# Top.net
KiCad netlist of a schematic drawn in Altium Designer
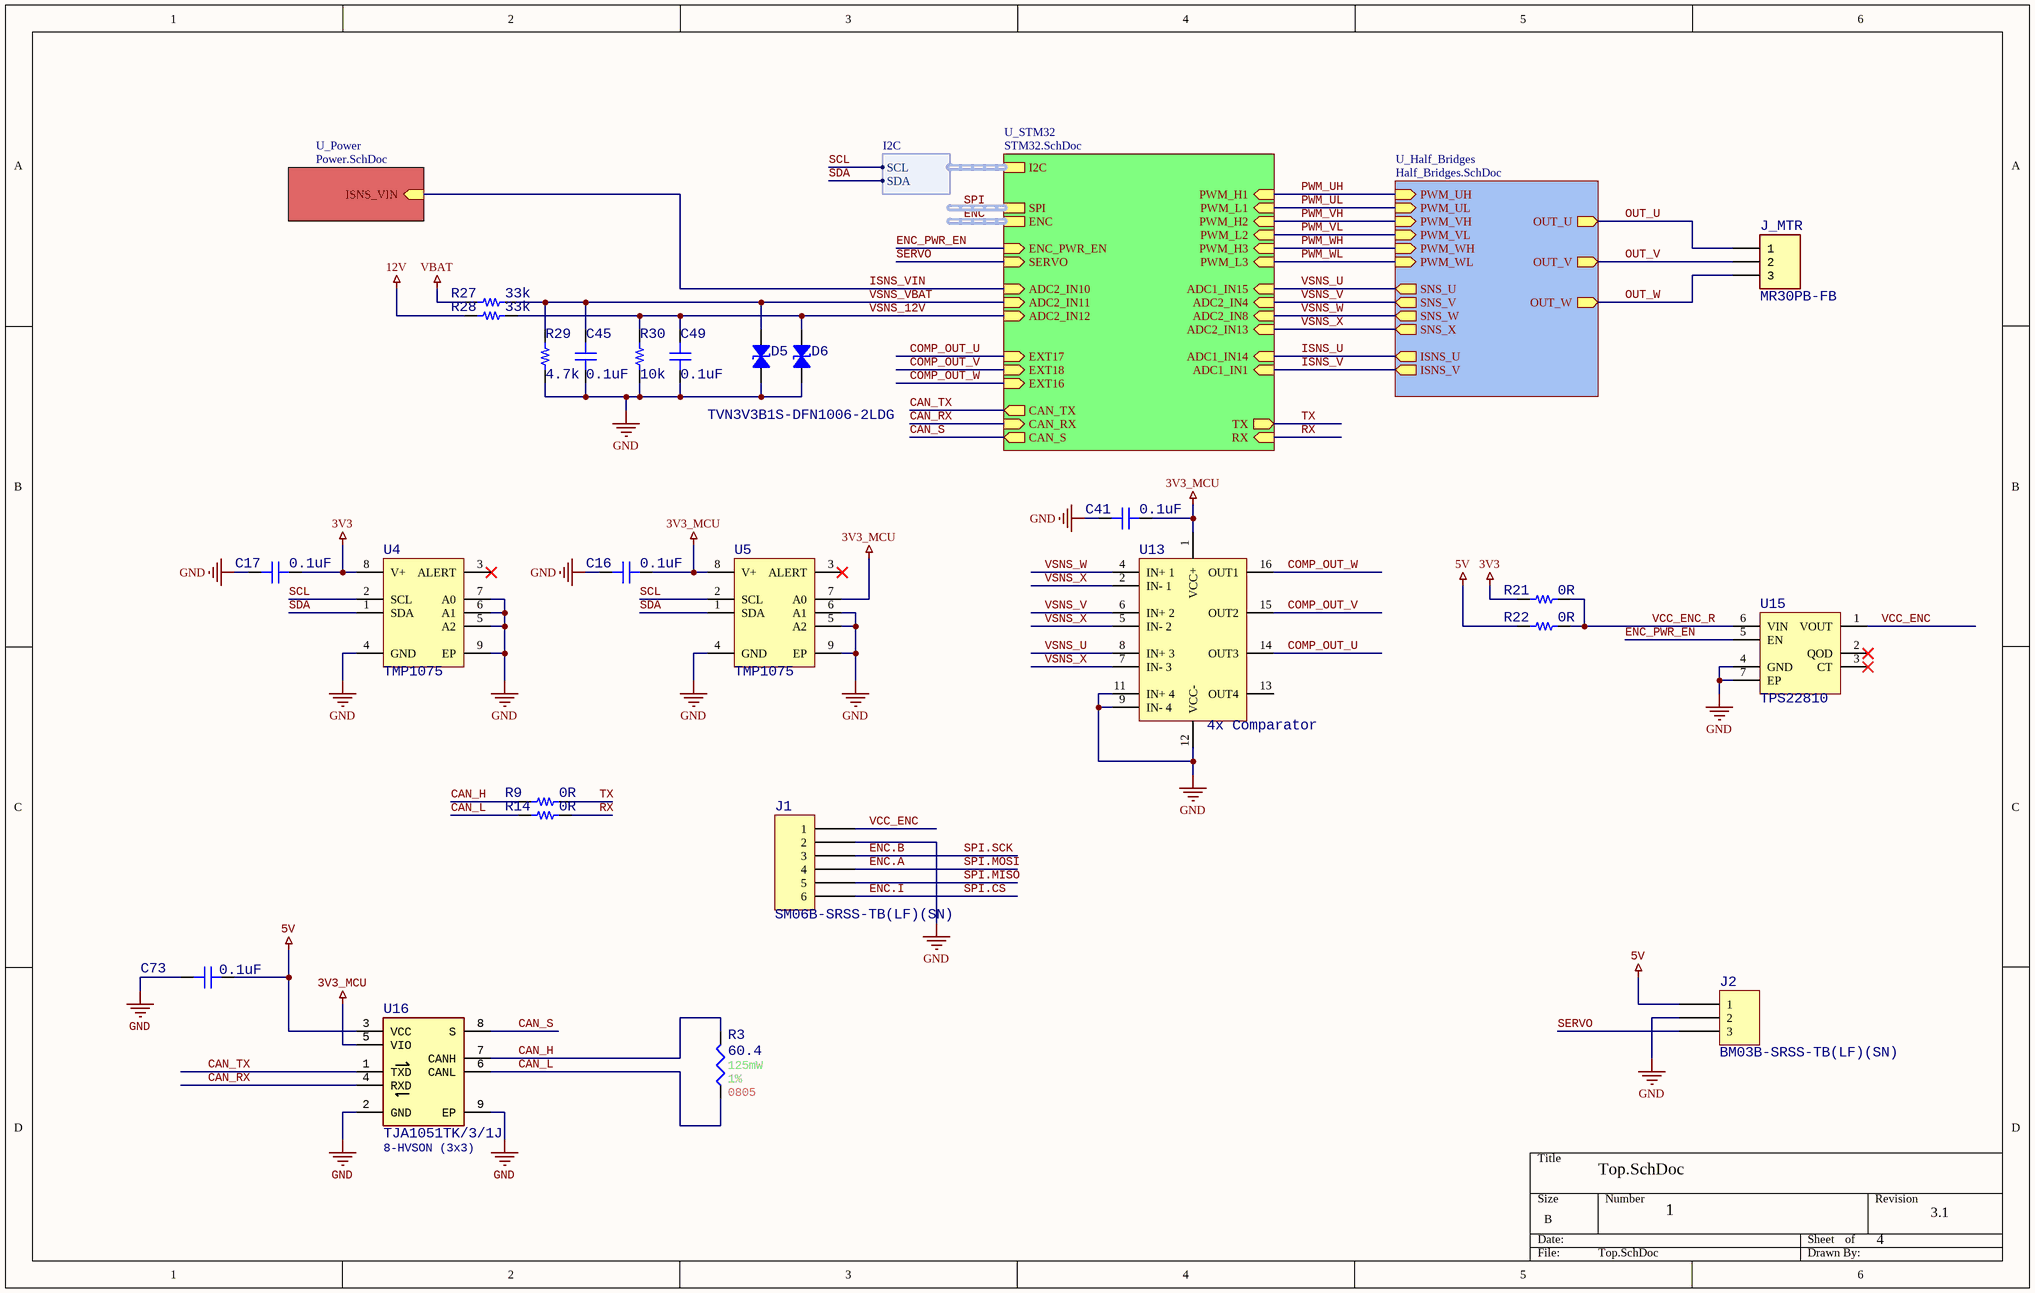
[diagram p0: Top.SchDoc]

(export (version "E")
  (design (tool "Eeschema 10.0.6"))
  (components
    (comp (ref "C16")
      (value "0.1uF")
      (footprint "CAP_0402")
      (description "CAP CER 402")
      (libsource (lib "IC") (part "CAP_0402"))
    )
    (comp (ref "C17")
      (value "0.1uF")
      (footprint "CAP_0402")
      (description "CAP CER 402")
      (libsource (lib "IC") (part "CAP_0402"))
    )
    (comp (ref "C41")
      (value "0.1uF")
      (footprint "CAP_0402")
      (description "CAP CER 402")
      (libsource (lib "IC") (part "CAP_0402"))
    )
    (comp (ref "C45")
      (value "0.1uF")
      (footprint "CAP_0402")
      (description "CAP CER 402")
      (libsource (lib "IC") (part "CAP_0402"))
    )
    (comp (ref "C49")
      (value "0.1uF")
      (footprint "CAP_0402")
      (description "CAP CER 402")
      (libsource (lib "IC") (part "CAP_0402"))
    )
    (comp (ref "C73")
      (value "0.1uF")
      (footprint "CAP_0402")
      (description "CAP CER 402")
      (libsource (lib "IC") (part "CAP_0402"))
    )
    (comp (ref "D5")
      (value "TVN3V3B1S-DFN1006-2LDG")
      (footprint "0402")
      (description "TVS DIODE 3.3V 14.2PF DFN1006")
      (fields (field (name "MANUFACTURER") "INPAQ Technology Co., Ltd"))
      (libsource (lib "Celestial Altium Library - altium_library") (part "Diode TVS"))
    )
    (comp (ref "D6")
      (value "TVN3V3B1S-DFN1006-2LDG")
      (footprint "0402")
      (description "TVS DIODE 3.3V 14.2PF DFN1006")
      (fields (field (name "MANUFACTURER") "INPAQ Technology Co., Ltd"))
      (libsource (lib "Celestial Altium Library - altium_library") (part "Diode TVS"))
    )
    (comp (ref "J1")
      (value "SM06B-SRSS-TB(LF)(SN)")
      (footprint "JST SM06B-SRSS-TB")
      (description "CONN HEADER SMD R/A 6POS 1MM")
      (fields (field (name "MANUFACTURER") "JST Sales America Inc."))
      (libsource (lib "Celestial Altium Library - altium_library") (part "6 Pin"))
    )
    (comp (ref "J2")
      (value "BM03B-SRSS-TB(LF)(SN)")
      (footprint "JST BM03B-SRSS-TB")
      (description "CONN HEADER SMD 3POS 1MM")
      (fields (field (name "MANUFACTURER") "JST Sales America Inc."))
      (libsource (lib "Celestial Altium Library - altium_library") (part "3 Pin"))
    )
    (comp (ref "J_MTR")
      (value "MR30PB-FB")
      (footprint "MR30PB-F")
      (description "Vertical 3 pin barrel connector")
      (fields (field (name "MANUFACTURER") "Amass"))
      (libsource (lib "Raise Robotics") (part "MR30PB-FB"))
    )
    (comp (ref "R3")
      (value "60.4")
      (footprint "0805 Resistor")
      (description "Res 60.4 Ohm 1% 1/8W 0805")
      (fields
        (field (name "POWER") "125mW")
        (field (name "TOLERANCE") "1%")
        (field (name "CASE/PACKAGE") "0805")
        (field (name "MANUFACTURER PART NUMBER") "TFA0805R60R4F-T5")
      )
      (libsource (lib "Raise Robotics") (part "Resistor"))
    )
    (comp (ref "R9")
      (value "0R")
      (footprint "RES_0402")
      (description "RES 0402")
      (libsource (lib "IC") (part "RES_0402"))
    )
    (comp (ref "R14")
      (value "0R")
      (footprint "RES_0402")
      (description "RES 0402")
      (libsource (lib "IC") (part "RES_0402"))
    )
    (comp (ref "R21")
      (value "0R")
      (footprint "RES_0402")
      (description "RES 0402")
      (libsource (lib "IC") (part "RES_0402"))
    )
    (comp (ref "R22")
      (value "0R")
      (footprint "RES_0402")
      (description "RES 0402")
      (libsource (lib "IC") (part "RES_0402"))
    )
    (comp (ref "R27")
      (value "33k")
      (footprint "RES_0402")
      (description "RES 0402")
      (libsource (lib "IC") (part "RES_0402"))
    )
    (comp (ref "R28")
      (value "33k")
      (footprint "RES_0402")
      (description "RES 0402")
      (libsource (lib "IC") (part "RES_0402"))
    )
    (comp (ref "R29")
      (value "4.7k")
      (footprint "RES_0402")
      (description "RES 0402")
      (libsource (lib "IC") (part "RES_0402"))
    )
    (comp (ref "R30")
      (value "10k")
      (footprint "RES_0402")
      (description "RES 0402")
      (libsource (lib "IC") (part "RES_0402"))
    )
    (comp (ref "U4")
      (value "TMP1075")
      (footprint "8_WSON_2x2_0.5mm")
      (description "I2C TEMP SENSOR")
      (libsource (lib "IC") (part "TMP1075"))
    )
    (comp (ref "U5")
      (value "TMP1075")
      (footprint "8_WSON_2x2_0.5mm")
      (description "I2C TEMP SENSOR")
      (libsource (lib "IC") (part "TMP1075"))
    )
    (comp (ref "U13")
      (value "4x Comparator")
      (footprint "QFN50P300X300X100-16N")
      (description "Comparator General Purpose CMOS, DTL, MOS, Open-Collector, TTL 16-QFN (3x3)")
      (libsource (lib "IC") (part "LM2901Q4T"))
    )
    (comp (ref "U15")
      (value "TPS22810")
      (footprint "6-WSON_2x2_0.65mm")
      (description "Load switch TPS22810DRVR")
      (libsource (lib "IC") (part "TPS22810DRVR"))
    )
    (comp (ref "U16")
      (value "TJA1051TK/3/1J")
      (footprint "TJA1044xxK")
      (description "Interface Circuit, PDSO8")
      (fields (field (name "CASE/PACKAGE") "8-HVSON (3x3)"))
      (libsource (lib "Raise Robotics") (part "TJA1044"))
    )
  )
  (nets
    (net (code "4") (name "/CAN_H") (class "Default")
      (node (ref "R3") (pin "2") (pinfunction "2_2") (pintype "passive"))
      (node (ref "R9") (pin "2") (pinfunction "2_2") (pintype "passive"))
      (node (ref "U16") (pin "7") (pinfunction "CANH_7") (pintype "passive"))
    )
    (net (code "5") (name "/CAN_L") (class "Default")
      (node (ref "R14") (pin "2") (pinfunction "2_2") (pintype "passive"))
      (node (ref "R3") (pin "1") (pinfunction "1_1") (pintype "passive"))
      (node (ref "U16") (pin "6") (pinfunction "CANL_6") (pintype "passive"))
    )
    (net (code "6") (name "/CAN_RX") (class "Default")
      (node (ref "U16") (pin "4") (pinfunction "RXD_4") (pintype "passive"))
    )
    (net (code "7") (name "/CAN_S") (class "Default")
      (node (ref "U16") (pin "8") (pinfunction "S_8") (pintype "passive"))
    )
    (net (code "8") (name "/CAN_TX") (class "Default")
      (node (ref "U16") (pin "1") (pinfunction "TXD_1") (pintype "passive"))
    )
    (net (code "9") (name "/COMP_OUT_U") (class "Default")
      (node (ref "U13") (pin "14") (pinfunction "OUT3_14") (pintype "passive"))
    )
    (net (code "10") (name "/COMP_OUT_V") (class "Default")
      (node (ref "U13") (pin "15") (pinfunction "OUT2_15") (pintype "passive"))
    )
    (net (code "11") (name "/COMP_OUT_W") (class "Default")
      (node (ref "U13") (pin "16") (pinfunction "OUT1_16") (pintype "passive"))
    )
    (net (code "12") (name "/ENC.A") (class "Default")
      (node (ref "J1") (pin "4") (pinfunction "4_4") (pintype "passive"))
    )
    (net (code "13") (name "/ENC.B") (class "Default")
      (node (ref "J1") (pin "3") (pinfunction "3_3") (pintype "passive"))
    )
    (net (code "14") (name "/ENC.I") (class "Default")
      (node (ref "J1") (pin "6") (pinfunction "6_6") (pintype "passive"))
    )
    (net (code "15") (name "/ENC_PWR_EN") (class "Default")
      (node (ref "U15") (pin "5") (pinfunction "EN_5") (pintype "passive"))
    )
    (net (code "19") (name "/OUT_U") (class "Default")
      (node (ref "J_MTR") (pin "1") (pinfunction "1_1") (pintype "passive"))
    )
    (net (code "20") (name "/OUT_V") (class "Default")
      (node (ref "J_MTR") (pin "2") (pinfunction "2_2") (pintype "passive"))
    )
    (net (code "21") (name "/OUT_W") (class "Default")
      (node (ref "J_MTR") (pin "3") (pinfunction "3_3") (pintype "passive"))
    )
    (net (code "28") (name "/RX") (class "Default")
      (node (ref "R14") (pin "1") (pinfunction "1_1") (pintype "passive"))
    )
    (net (code "29") (name "/SCL") (class "Default")
      (node (ref "U4") (pin "2") (pinfunction "SCL_2") (pintype "passive"))
      (node (ref "U5") (pin "2") (pinfunction "SCL_2") (pintype "passive"))
    )
    (net (code "30") (name "/SDA") (class "Default")
      (node (ref "U4") (pin "1") (pinfunction "SDA_1") (pintype "passive"))
      (node (ref "U5") (pin "1") (pinfunction "SDA_1") (pintype "passive"))
    )
    (net (code "31") (name "/SERVO") (class "Default")
      (node (ref "J2") (pin "3") (pinfunction "3_3") (pintype "passive"))
    )
    (net (code "32") (name "/SPI.MISO") (class "Default")
      (node (ref "J1") (pin "5") (pinfunction "5_5") (pintype "passive"))
    )
    (net (code "33") (name "/TX") (class "Default")
      (node (ref "R9") (pin "1") (pinfunction "1_1") (pintype "passive"))
    )
    (net (code "34") (name "/VCC_ENC") (class "Default")
      (node (ref "J1") (pin "1") (pinfunction "1_1") (pintype "passive"))
      (node (ref "U15") (pin "1") (pinfunction "VOUT_1") (pintype "passive"))
    )
    (net (code "35") (name "/VCC_ENC_R") (class "Default")
      (node (ref "R21") (pin "1") (pinfunction "1_1") (pintype "passive"))
      (node (ref "R22") (pin "1") (pinfunction "1_1") (pintype "passive"))
      (node (ref "U15") (pin "6") (pinfunction "VIN_6") (pintype "passive"))
    )
    (net (code "36") (name "/VSNS_12V") (class "Default")
      (node (ref "C49") (pin "2") (pinfunction "2_2") (pintype "passive"))
      (node (ref "D6") (pin "2") (pinfunction "2_2") (pintype "passive"))
      (node (ref "R28") (pin "1") (pinfunction "1_1") (pintype "passive"))
      (node (ref "R30") (pin "1") (pinfunction "1_1") (pintype "passive"))
    )
    (net (code "37") (name "/VSNS_U") (class "Default")
      (node (ref "U13") (pin "8") (pinfunction "IN+_3_8") (pintype "passive"))
    )
    (net (code "38") (name "/VSNS_V") (class "Default")
      (node (ref "U13") (pin "6") (pinfunction "IN+_2_6") (pintype "passive"))
    )
    (net (code "39") (name "/VSNS_VBAT") (class "Default")
      (node (ref "C45") (pin "2") (pinfunction "2_2") (pintype "passive"))
      (node (ref "D5") (pin "2") (pinfunction "2_2") (pintype "passive"))
      (node (ref "R27") (pin "1") (pinfunction "1_1") (pintype "passive"))
      (node (ref "R29") (pin "1") (pinfunction "1_1") (pintype "passive"))
    )
    (net (code "40") (name "/VSNS_W") (class "Default")
      (node (ref "U13") (pin "4") (pinfunction "IN+_1_4") (pintype "passive"))
    )
    (net (code "41") (name "/VSNS_X") (class "Default")
      (node (ref "U13") (pin "2") (pinfunction "IN-_1_2") (pintype "passive"))
      (node (ref "U13") (pin "5") (pinfunction "IN-_2_5") (pintype "passive"))
      (node (ref "U13") (pin "7") (pinfunction "IN-_3_7") (pintype "passive"))
    )
    (net (code "45") (name "3V3") (class "Default")
      (node (ref "C17") (pin "2") (pinfunction "2_2") (pintype "passive"))
      (node (ref "R21") (pin "2") (pinfunction "2_2") (pintype "passive"))
      (node (ref "U4") (pin "8") (pinfunction "V+_8") (pintype "passive"))
    )
    (net (code "46") (name "3V3_MCU") (class "Default")
      (node (ref "C16") (pin "2") (pinfunction "2_2") (pintype "passive"))
      (node (ref "C41") (pin "2") (pinfunction "2_2") (pintype "passive"))
      (node (ref "U13") (pin "1") (pinfunction "VCC+_1") (pintype "passive"))
      (node (ref "U16") (pin "5") (pinfunction "VIO_5") (pintype "passive"))
      (node (ref "U5") (pin "7") (pinfunction "A0_7") (pintype "passive"))
      (node (ref "U5") (pin "8") (pinfunction "V+_8") (pintype "passive"))
    )
    (net (code "47") (name "5V") (class "Default")
      (node (ref "C73") (pin "1") (pinfunction "1_1") (pintype "passive"))
      (node (ref "J2") (pin "1") (pinfunction "1_1") (pintype "passive"))
      (node (ref "R22") (pin "2") (pinfunction "2_2") (pintype "passive"))
      (node (ref "U16") (pin "3") (pinfunction "VCC_3") (pintype "passive"))
    )
    (net (code "48") (name "12V") (class "Default")
      (node (ref "R28") (pin "2") (pinfunction "2_2") (pintype "passive"))
    )
    (net (code "49") (name "GND") (class "Default")
      (node (ref "C16") (pin "1") (pinfunction "1_1") (pintype "passive"))
      (node (ref "C17") (pin "1") (pinfunction "1_1") (pintype "passive"))
      (node (ref "C41") (pin "1") (pinfunction "1_1") (pintype "passive"))
      (node (ref "C45") (pin "1") (pinfunction "1_1") (pintype "passive"))
      (node (ref "C49") (pin "1") (pinfunction "1_1") (pintype "passive"))
      (node (ref "C73") (pin "2") (pinfunction "2_2") (pintype "passive"))
      (node (ref "D5") (pin "1") (pinfunction "1_1") (pintype "passive"))
      (node (ref "D6") (pin "1") (pinfunction "1_1") (pintype "passive"))
      (node (ref "J1") (pin "2") (pinfunction "2_2") (pintype "passive"))
      (node (ref "J2") (pin "2") (pinfunction "2_2") (pintype "passive"))
      (node (ref "R29") (pin "2") (pinfunction "2_2") (pintype "passive"))
      (node (ref "R30") (pin "2") (pinfunction "2_2") (pintype "passive"))
      (node (ref "U13") (pin "11") (pinfunction "IN+_4_11") (pintype "passive"))
      (node (ref "U13") (pin "12") (pinfunction "VCC-_12") (pintype "passive"))
      (node (ref "U13") (pin "9") (pinfunction "IN-_4_9") (pintype "passive"))
      (node (ref "U15") (pin "4") (pinfunction "GND_4") (pintype "passive"))
      (node (ref "U15") (pin "7") (pinfunction "EP_7") (pintype "passive"))
      (node (ref "U16") (pin "2") (pinfunction "GND_2") (pintype "passive"))
      (node (ref "U16") (pin "9") (pinfunction "EP_9") (pintype "passive"))
      (node (ref "U4") (pin "4") (pinfunction "GND_4") (pintype "passive"))
      (node (ref "U4") (pin "5") (pinfunction "A2_5") (pintype "passive"))
      (node (ref "U4") (pin "6") (pinfunction "A1_6") (pintype "passive"))
      (node (ref "U4") (pin "7") (pinfunction "A0_7") (pintype "passive"))
      (node (ref "U4") (pin "9") (pinfunction "EP_9") (pintype "passive"))
      (node (ref "U5") (pin "4") (pinfunction "GND_4") (pintype "passive"))
      (node (ref "U5") (pin "5") (pinfunction "A2_5") (pintype "passive"))
      (node (ref "U5") (pin "6") (pinfunction "A1_6") (pintype "passive"))
      (node (ref "U5") (pin "9") (pinfunction "EP_9") (pintype "passive"))
    )
    (net (code "50") (name "VBAT") (class "Default")
      (node (ref "R27") (pin "2") (pinfunction "2_2") (pintype "passive"))
    )
    (net (code "51") (name "unconnected-(U4-ALERT-Pad3)") (class "Default")
      (node (ref "U4") (pin "3") (pinfunction "ALERT_3") (pintype "passive+no_connect"))
    )
    (net (code "52") (name "unconnected-(U5-ALERT-Pad3)") (class "Default")
      (node (ref "U5") (pin "3") (pinfunction "ALERT_3") (pintype "passive+no_connect"))
    )
    (net (code "53") (name "unconnected-(U13-OUT4-Pad13)") (class "Default")
      (node (ref "U13") (pin "13") (pinfunction "OUT4_13") (pintype "passive"))
    )
    (net (code "54") (name "unconnected-(U15-CT-Pad3)") (class "Default")
      (node (ref "U15") (pin "3") (pinfunction "CT_3") (pintype "passive+no_connect"))
    )
    (net (code "55") (name "unconnected-(U15-QOD-Pad2)") (class "Default")
      (node (ref "U15") (pin "2") (pinfunction "QOD_2") (pintype "passive+no_connect"))
    )
  )
)
